# FubarinoMini_v16.net
KiCad netlist of a schematic drawn in EAGLE
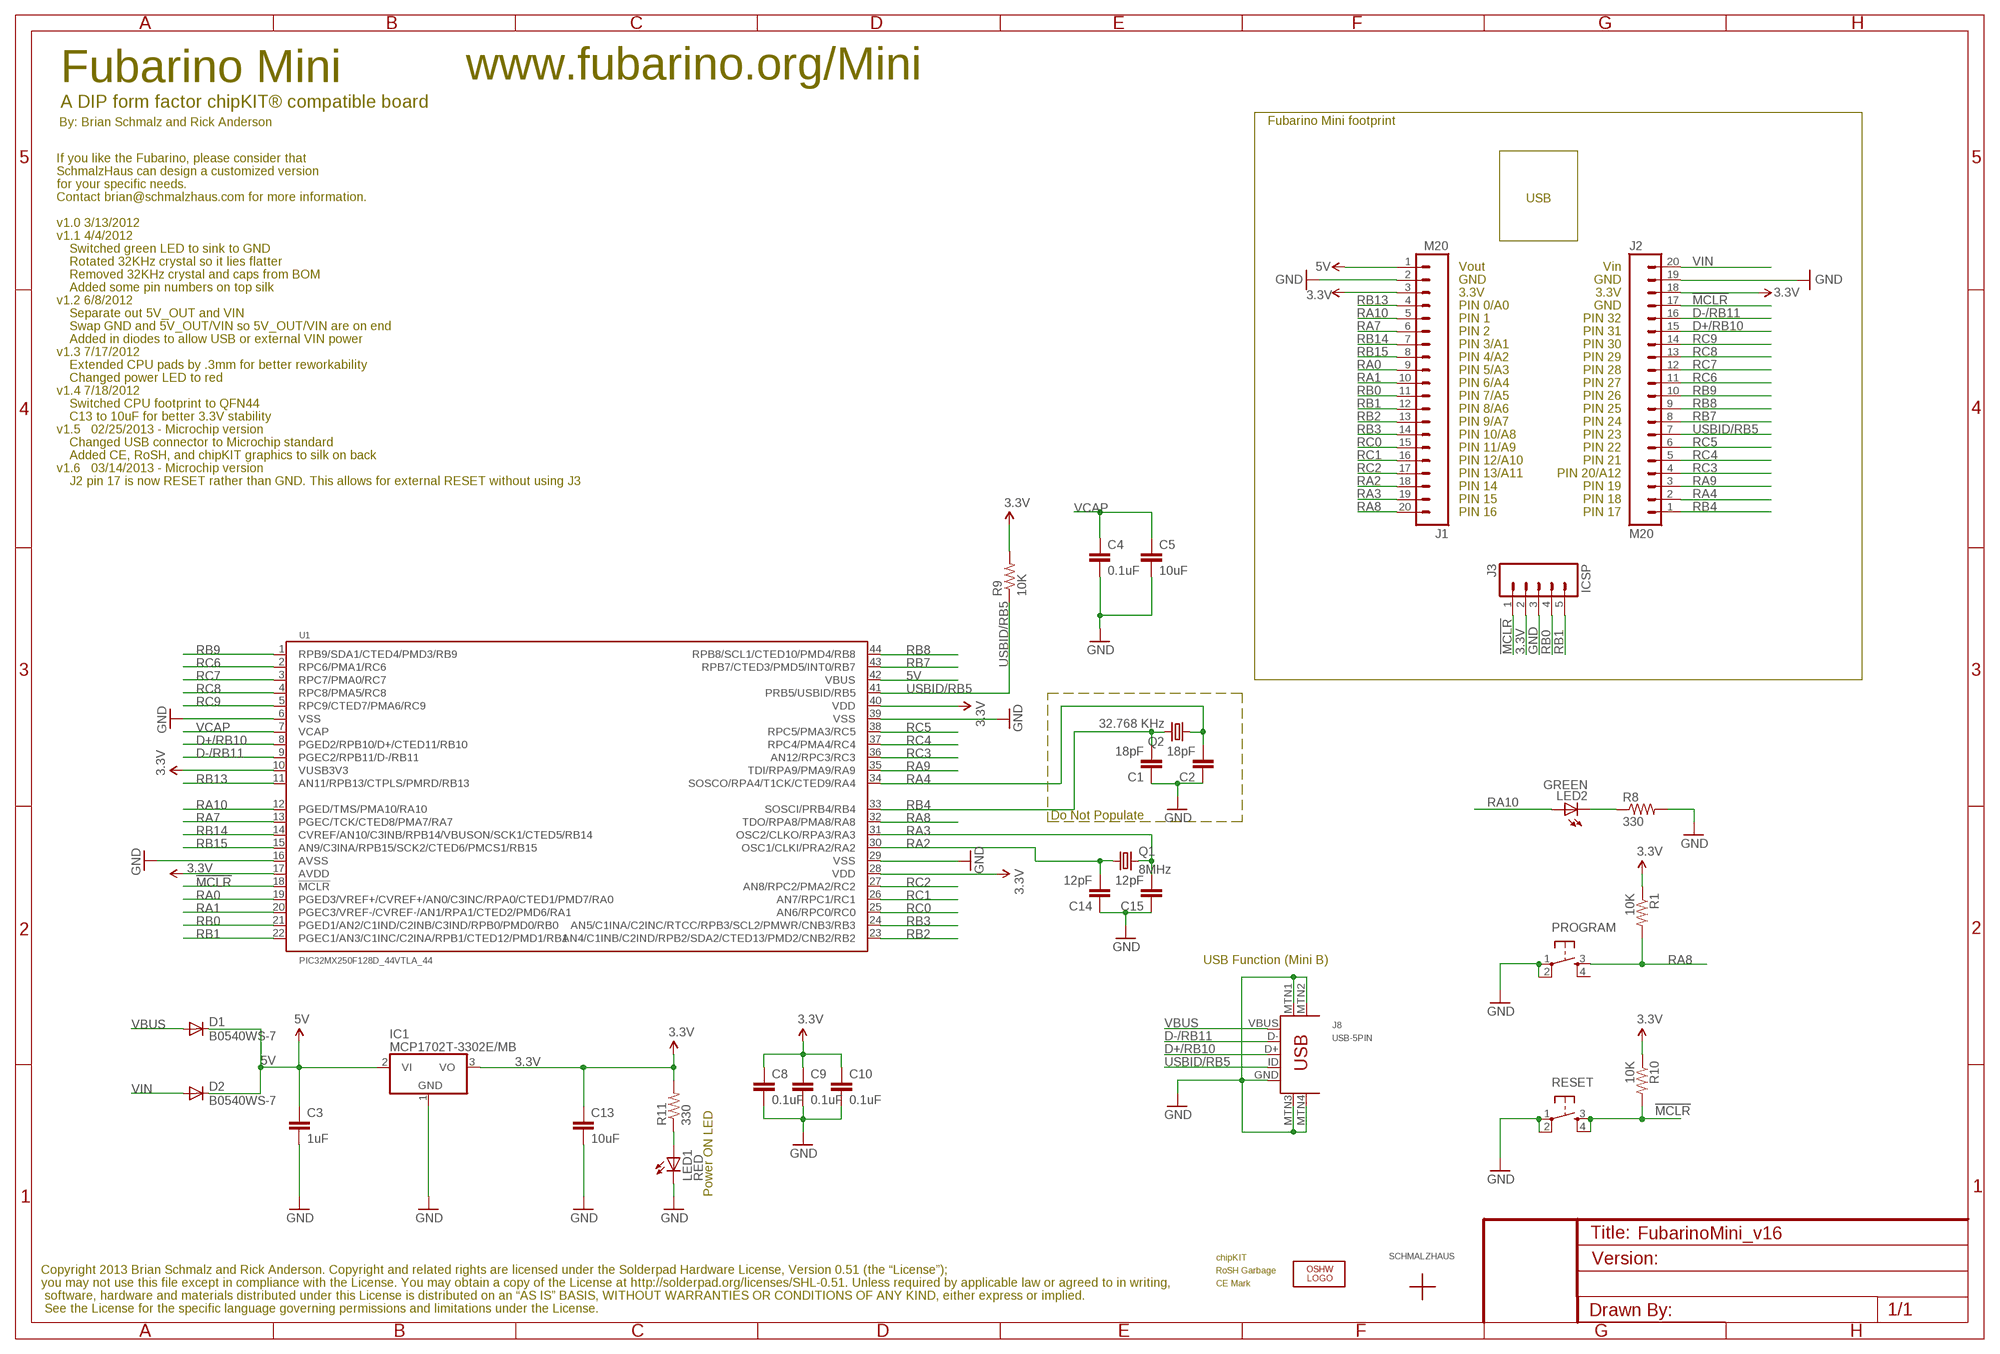
[diagram p0: schematic, sheet 1]

(export (version "E")
  (design (tool "Eeschema 10.0.6"))
  (components
    (comp (ref "C1")
      (value "18pF")
      (footprint "eagle-import:0603-CAP")
      (libsource (lib "eagle-import") (part "SparkFun_CAP0603-CAP"))
    )
    (comp (ref "C2")
      (value "18pF")
      (footprint "eagle-import:0603-CAP")
      (libsource (lib "eagle-import") (part "SparkFun_CAP0603-CAP"))
    )
    (comp (ref "C3")
      (value "1uF")
      (footprint "eagle-import:0603-CAP")
      (libsource (lib "eagle-import") (part "SparkFun_CAP0603-CAP"))
    )
    (comp (ref "C4")
      (value "0.1uF")
      (footprint "eagle-import:0603-CAP")
      (libsource (lib "eagle-import") (part "SparkFun_CAP0603-CAP"))
    )
    (comp (ref "C5")
      (value "10uF")
      (footprint "eagle-import:0805")
      (libsource (lib "eagle-import") (part "CAP0805"))
    )
    (comp (ref "C8")
      (value "0.1uF")
      (footprint "eagle-import:0603-CAP")
      (libsource (lib "eagle-import") (part "SparkFun_CAP0603-CAP"))
    )
    (comp (ref "C9")
      (value "0.1uF")
      (footprint "eagle-import:0603-CAP")
      (libsource (lib "eagle-import") (part "SparkFun_CAP0603-CAP"))
    )
    (comp (ref "C10")
      (value "0.1uF")
      (footprint "eagle-import:0603")
      (libsource (lib "eagle-import") (part "CAP0603"))
    )
    (comp (ref "C13")
      (value "10uF")
      (footprint "eagle-import:0805")
      (libsource (lib "eagle-import") (part "SparkFun02-20-08_CAP0805"))
    )
    (comp (ref "C14")
      (value "12pF")
      (footprint "eagle-import:0603-CAP")
      (libsource (lib "eagle-import") (part "SparkFun_CAP0603-CAP"))
    )
    (comp (ref "C15")
      (value "12pF")
      (footprint "eagle-import:0603-CAP")
      (libsource (lib "eagle-import") (part "SparkFun_CAP0603-CAP"))
    )
    (comp (ref "D1")
      (value "B0540WS-7")
      (footprint "eagle-import:SOD-323")
      (libsource (lib "eagle-import") (part "DIODESOD"))
    )
    (comp (ref "D2")
      (value "B0540WS-7")
      (footprint "eagle-import:SOD-323")
      (libsource (lib "eagle-import") (part "DIODESOD"))
    )
    (comp (ref "IC1")
      (value "MCP1702T-3302E/MB")
      (footprint "eagle-import:SOT89")
      (libsource (lib "eagle-import") (part "MCP1703MB33"))
    )
    (comp (ref "ICSP")
      (value "J3")
      (footprint "eagle-import:1X05_NOSILK")
      (libsource (lib "eagle-import") (part "M05NOSLILK"))
    )
    (comp (ref "J1")
      (value "M20")
      (footprint "eagle-import:1X20_NO_PIN1")
      (libsource (lib "eagle-import") (part "M20"))
    )
    (comp (ref "J2")
      (value "M20")
      (footprint "eagle-import:1X20_NO_PIN1")
      (libsource (lib "eagle-import") (part "M20"))
    )
    (comp (ref "J8")
      (value "USB-5PIN")
      (footprint "eagle-import:USB-MINIB-5PIN-HIROSE-UX60-MB-5ST")
      (libsource (lib "eagle-import") (part "USB-5PIN"))
    )
    (comp (ref "LED1")
      (value "RED")
      (footprint "eagle-import:LED-0603")
      (libsource (lib "eagle-import") (part "LED0603"))
    )
    (comp (ref "LED2")
      (value "GREEN")
      (footprint "eagle-import:LED-0603")
      (libsource (lib "eagle-import") (part "LED0603"))
    )
    (comp (ref "LOGO1")
      (value "OSHW_LOGO_8MILX0070-NT")
      (footprint "eagle-import:OSHW_8X70_NOTEXT")
      (libsource (lib "eagle-import") (part "OSHW_LOGO_8MILX0070-NT"))
    )
    (comp (ref "PROGRAM")
      (value "TAC_SWITCHSND")
      (footprint "eagle-import:TACTILE_SWITCH_SMD")
      (libsource (lib "eagle-import") (part "TAC_SWITCHSND"))
    )
    (comp (ref "Q1")
      (value "8MHz")
      (footprint "eagle-import:NX5032_5MM_3.2MM_CRYSTAL")
      (libsource (lib "eagle-import") (part "CRYSTALNX5032"))
    )
    (comp (ref "Q2")
      (value "32.768 KHz")
      (footprint "eagle-import:TC26H")
      (libsource (lib "eagle-import") (part "CRYSTALTC26H"))
    )
    (comp (ref "R1")
      (value "10K")
      (footprint "eagle-import:0603-RES")
      (libsource (lib "eagle-import") (part "RESISTOR0603-RES"))
    )
    (comp (ref "R8")
      (value "330")
      (footprint "eagle-import:0603-RES")
      (libsource (lib "eagle-import") (part "RESISTOR0603-RES"))
    )
    (comp (ref "R9")
      (value "10K")
      (footprint "eagle-import:0603-RES")
      (libsource (lib "eagle-import") (part "RESISTOR0603-RES"))
    )
    (comp (ref "R10")
      (value "10K")
      (footprint "eagle-import:0603-RES")
      (libsource (lib "eagle-import") (part "RESISTOR0603-RES"))
    )
    (comp (ref "R11")
      (value "330")
      (footprint "eagle-import:0603-RES")
      (libsource (lib "eagle-import") (part "RESISTOR0603-RES"))
    )
    (comp (ref "RESET")
      (value "TAC_SWITCHSND")
      (footprint "eagle-import:TACTILE_SWITCH_SMD")
      (libsource (lib "eagle-import") (part "TAC_SWITCHSND"))
    )
    (comp (ref "U$1")
      (value "SCHMALZHAUSSCHMALZHAUS_SMALL")
      (footprint "eagle-import:SCHMALZHAUS_SMALL")
      (libsource (lib "eagle-import") (part "SCHMALZHAUSSCHMALZHAUS_SMALL"))
    )
    (comp (ref "U$2")
      (value "CE_MARK5MM")
      (footprint "eagle-import:CE_5MM")
      (libsource (lib "eagle-import") (part "CE_MARK5MM"))
    )
    (comp (ref "U$3")
      (value "ROSH_GARBAGE")
      (footprint "eagle-import:ROHS_GARBAGE_5MM")
      (libsource (lib "eagle-import") (part "ROSH_GARBAGE"))
    )
    (comp (ref "U$4")
      (value "CHIPKIT2MM")
      (footprint "eagle-import:CHIPKIT_2MM")
      (libsource (lib "eagle-import") (part "CHIPKIT2MM"))
    )
    (comp (ref "U1")
      (value "PIC32MX250F128D_44VTLA_44")
      (footprint "eagle-import:QFN-44-8X8-NOPAD")
      (libsource (lib "eagle-import") (part "PIC32MX2XX_44QFN44"))
    )
  )
  (nets
    (net (code "1") (name "/D+{slash}RB10") (class "Default")
      (node (ref "J2") (pin "15") (pinfunction "15_15") (pintype "passive"))
      (node (ref "J8") (pin "D+") (pinfunction "D+_D+") (pintype "bidirectional"))
      (node (ref "U1") (pin "8") (pinfunction "PGED2/RPB10/D+/CTED11/RB10_8") (pintype "bidirectional"))
    )
    (net (code "2") (name "/D-{slash}RB11") (class "Default")
      (node (ref "J2") (pin "16") (pinfunction "16_16") (pintype "passive"))
      (node (ref "J8") (pin "D-") (pinfunction "D-_D-") (pintype "bidirectional"))
      (node (ref "U1") (pin "9") (pinfunction "PGEC2/RPB11/D-/RB11_9") (pintype "bidirectional"))
    )
    (net (code "3") (name "/RA0") (class "Default")
      (node (ref "J1") (pin "9") (pinfunction "9_9") (pintype "passive"))
      (node (ref "U1") (pin "19") (pinfunction "PGED3/VREF+/CVREF+/AN0/C3INC/RPA0/CTED1/PMD7/RA0_19") (pintype "bidirectional"))
    )
    (net (code "4") (name "/RA1") (class "Default")
      (node (ref "J1") (pin "10") (pinfunction "10_10") (pintype "passive"))
      (node (ref "U1") (pin "20") (pinfunction "PGEC3/VREF-/CVREF-/AN1/RPA1/CTED2/PMD6/RA1_20") (pintype "bidirectional"))
    )
    (net (code "5") (name "/RA2") (class "Default")
      (node (ref "C14") (pin "2") (pinfunction "2_2") (pintype "passive"))
      (node (ref "J1") (pin "18") (pinfunction "18_18") (pintype "passive"))
      (node (ref "Q1") (pin "1") (pinfunction "1_1") (pintype "passive"))
      (node (ref "U1") (pin "30") (pinfunction "OSC1/CLKI/PRA2/RA2_30") (pintype "bidirectional"))
    )
    (net (code "6") (name "/RA3") (class "Default")
      (node (ref "C15") (pin "2") (pinfunction "2_2") (pintype "passive"))
      (node (ref "J1") (pin "19") (pinfunction "19_19") (pintype "passive"))
      (node (ref "Q1") (pin "2") (pinfunction "2_2") (pintype "passive"))
      (node (ref "U1") (pin "31") (pinfunction "OSC2/CLKO/RPA3/RA3_31") (pintype "bidirectional"))
    )
    (net (code "7") (name "/RA4") (class "Default")
      (node (ref "C2") (pin "2") (pinfunction "2_2") (pintype "passive"))
      (node (ref "J2") (pin "2") (pinfunction "2_2") (pintype "passive"))
      (node (ref "Q2") (pin "1") (pinfunction "1_1") (pintype "passive"))
      (node (ref "U1") (pin "34") (pinfunction "SOSCO/RPA4/T1CK/CTED9/RA4_34") (pintype "bidirectional"))
    )
    (net (code "8") (name "/RA7") (class "Default")
      (node (ref "J1") (pin "6") (pinfunction "6_6") (pintype "passive"))
      (node (ref "U1") (pin "13") (pinfunction "PGEC/TCK/CTED8/PMA7/RA7_13") (pintype "bidirectional"))
    )
    (net (code "9") (name "/RA8") (class "Default")
      (node (ref "J1") (pin "20") (pinfunction "20_20") (pintype "passive"))
      (node (ref "PROGRAM") (pin "3") (pinfunction "3_3") (pintype "passive"))
      (node (ref "R1") (pin "2") (pinfunction "2_2") (pintype "passive"))
      (node (ref "U1") (pin "32") (pinfunction "TDO/RPA8/PMA8/RA8_32") (pintype "bidirectional"))
    )
    (net (code "10") (name "/RA9") (class "Default")
      (node (ref "J2") (pin "3") (pinfunction "3_3") (pintype "passive"))
      (node (ref "U1") (pin "35") (pinfunction "TDI/RPA9/PMA9/RA9_35") (pintype "bidirectional"))
    )
    (net (code "11") (name "/RA10") (class "Default")
      (node (ref "J1") (pin "5") (pinfunction "5_5") (pintype "passive"))
      (node (ref "LED2") (pin "A") (pinfunction "A_A") (pintype "passive"))
      (node (ref "U1") (pin "12") (pinfunction "PGED/TMS/PMA10/RA10_12") (pintype "bidirectional"))
    )
    (net (code "12") (name "/RB0") (class "Default")
      (node (ref "ICSP") (pin "4") (pinfunction "4_4") (pintype "passive"))
      (node (ref "J1") (pin "11") (pinfunction "11_11") (pintype "passive"))
      (node (ref "U1") (pin "21") (pinfunction "PGED1/AN2/C1IND/C2INB/C3IND/RPB0/PMD0/RB0_21") (pintype "bidirectional"))
    )
    (net (code "13") (name "/RB1") (class "Default")
      (node (ref "ICSP") (pin "5") (pinfunction "5_5") (pintype "passive"))
      (node (ref "J1") (pin "12") (pinfunction "12_12") (pintype "passive"))
      (node (ref "U1") (pin "22") (pinfunction "PGEC1/AN3/C1INC/C2INA/RPB1/CTED12/PMD1/RB1_22") (pintype "bidirectional"))
    )
    (net (code "14") (name "/RB2") (class "Default")
      (node (ref "J1") (pin "13") (pinfunction "13_13") (pintype "passive"))
      (node (ref "U1") (pin "23") (pinfunction "AN4/C1INB/C2IND/RPB2/SDA2/CTED13/PMD2/CNB2/RB2_23") (pintype "bidirectional"))
    )
    (net (code "15") (name "/RB3") (class "Default")
      (node (ref "J1") (pin "14") (pinfunction "14_14") (pintype "passive"))
      (node (ref "U1") (pin "24") (pinfunction "AN5/C1INA/C2INC/RTCC/RPB3/SCL2/PMWR/CNB3/RB3_24") (pintype "bidirectional"))
    )
    (net (code "16") (name "/RB4") (class "Default")
      (node (ref "C1") (pin "2") (pinfunction "2_2") (pintype "passive"))
      (node (ref "J2") (pin "1") (pinfunction "1_1") (pintype "passive"))
      (node (ref "Q2") (pin "2") (pinfunction "2_2") (pintype "passive"))
      (node (ref "U1") (pin "33") (pinfunction "SOSCI/PRB4/RB4_33") (pintype "bidirectional"))
    )
    (net (code "17") (name "/RB7") (class "Default")
      (node (ref "J2") (pin "8") (pinfunction "8_8") (pintype "passive"))
      (node (ref "U1") (pin "43") (pinfunction "RPB7/CTED3/PMD5/INT0/RB7_43") (pintype "bidirectional"))
    )
    (net (code "18") (name "/RB8") (class "Default")
      (node (ref "J2") (pin "9") (pinfunction "9_9") (pintype "passive"))
      (node (ref "U1") (pin "44") (pinfunction "RPB8/SCL1/CTED10/PMD4/RB8_44") (pintype "bidirectional"))
    )
    (net (code "19") (name "/RB9") (class "Default")
      (node (ref "J2") (pin "10") (pinfunction "10_10") (pintype "passive"))
      (node (ref "U1") (pin "1") (pinfunction "RPB9/SDA1/CTED4/PMD3/RB9_1") (pintype "bidirectional"))
    )
    (net (code "20") (name "/RB13") (class "Default")
      (node (ref "J1") (pin "4") (pinfunction "4_4") (pintype "passive"))
      (node (ref "U1") (pin "11") (pinfunction "AN11/RPB13/CTPLS/PMRD/RB13_11") (pintype "bidirectional"))
    )
    (net (code "21") (name "/RB14") (class "Default")
      (node (ref "J1") (pin "7") (pinfunction "7_7") (pintype "passive"))
      (node (ref "U1") (pin "14") (pinfunction "CVREF/AN10/C3INB/RPB14/VBUSON/SCK1/CTED5/RB14_14") (pintype "bidirectional"))
    )
    (net (code "22") (name "/RB15") (class "Default")
      (node (ref "J1") (pin "8") (pinfunction "8_8") (pintype "passive"))
      (node (ref "U1") (pin "15") (pinfunction "AN9/C3INA/RPB15/SCK2/CTED6/PMCS1/RB15_15") (pintype "bidirectional"))
    )
    (net (code "23") (name "/RC0") (class "Default")
      (node (ref "J1") (pin "15") (pinfunction "15_15") (pintype "passive"))
      (node (ref "U1") (pin "25") (pinfunction "AN6/RPC0/RC0_25") (pintype "bidirectional"))
    )
    (net (code "24") (name "/RC1") (class "Default")
      (node (ref "J1") (pin "16") (pinfunction "16_16") (pintype "passive"))
      (node (ref "U1") (pin "26") (pinfunction "AN7/RPC1/RC1_26") (pintype "bidirectional"))
    )
    (net (code "25") (name "/RC2") (class "Default")
      (node (ref "J1") (pin "17") (pinfunction "17_17") (pintype "passive"))
      (node (ref "U1") (pin "27") (pinfunction "AN8/RPC2/PMA2/RC2_27") (pintype "bidirectional"))
    )
    (net (code "26") (name "/RC3") (class "Default")
      (node (ref "J2") (pin "4") (pinfunction "4_4") (pintype "passive"))
      (node (ref "U1") (pin "36") (pinfunction "AN12/RPC3/RC3_36") (pintype "bidirectional"))
    )
    (net (code "27") (name "/RC4") (class "Default")
      (node (ref "J2") (pin "5") (pinfunction "5_5") (pintype "passive"))
      (node (ref "U1") (pin "37") (pinfunction "RPC4/PMA4/RC4_37") (pintype "bidirectional"))
    )
    (net (code "28") (name "/RC5") (class "Default")
      (node (ref "J2") (pin "6") (pinfunction "6_6") (pintype "passive"))
      (node (ref "U1") (pin "38") (pinfunction "RPC5/PMA3/RC5_38") (pintype "bidirectional"))
    )
    (net (code "29") (name "/RC6") (class "Default")
      (node (ref "J2") (pin "11") (pinfunction "11_11") (pintype "passive"))
      (node (ref "U1") (pin "2") (pinfunction "RPC6/PMA1/RC6_2") (pintype "bidirectional"))
    )
    (net (code "30") (name "/RC7") (class "Default")
      (node (ref "J2") (pin "12") (pinfunction "12_12") (pintype "passive"))
      (node (ref "U1") (pin "3") (pinfunction "RPC7/PMA0/RC7_3") (pintype "bidirectional"))
    )
    (net (code "31") (name "/RC8") (class "Default")
      (node (ref "J2") (pin "13") (pinfunction "13_13") (pintype "passive"))
      (node (ref "U1") (pin "4") (pinfunction "RPC8/PMA5/RC8_4") (pintype "bidirectional"))
    )
    (net (code "32") (name "/RC9") (class "Default")
      (node (ref "J2") (pin "14") (pinfunction "14_14") (pintype "passive"))
      (node (ref "U1") (pin "5") (pinfunction "RPC9/CTED7/PMA6/RC9_5") (pintype "bidirectional"))
    )
    (net (code "33") (name "/USBID{slash}RB5") (class "Default")
      (node (ref "J2") (pin "7") (pinfunction "7_7") (pintype "passive"))
      (node (ref "J8") (pin "ID") (pinfunction "ID_ID") (pintype "bidirectional"))
      (node (ref "R9") (pin "1") (pinfunction "1_1") (pintype "passive"))
      (node (ref "U1") (pin "41") (pinfunction "PRB5/USBID/RB5_41") (pintype "bidirectional"))
    )
    (net (code "34") (name "/VBUS") (class "Default")
      (node (ref "D1") (pin "2") (pinfunction "A_2") (pintype "passive"))
      (node (ref "J8") (pin "VBUS") (pinfunction "VBUS_VBUS") (pintype "bidirectional"))
    )
    (net (code "35") (name "/VCAP") (class "Default")
      (node (ref "C4") (pin "1") (pinfunction "1_1") (pintype "passive"))
      (node (ref "C5") (pin "1") (pinfunction "1_1") (pintype "passive"))
      (node (ref "U1") (pin "7") (pinfunction "VCAP_7") (pintype "bidirectional"))
    )
    (net (code "36") (name "/VIN") (class "Default")
      (node (ref "D2") (pin "2") (pinfunction "A_2") (pintype "passive"))
      (node (ref "J2") (pin "20") (pinfunction "20_20") (pintype "passive"))
    )
    (net (code "37") (name "/~{MCLR}") (class "Default")
      (node (ref "ICSP") (pin "1") (pinfunction "1_1") (pintype "passive"))
      (node (ref "J2") (pin "17") (pinfunction "17_17") (pintype "passive"))
      (node (ref "R10") (pin "2") (pinfunction "2_2") (pintype "passive"))
      (node (ref "RESET") (pin "3") (pinfunction "3_3") (pintype "passive"))
      (node (ref "RESET") (pin "4") (pinfunction "4_4") (pintype "passive"))
      (node (ref "U1") (pin "18") (pinfunction "~{MCLR}_18") (pintype "bidirectional"))
    )
    (net (code "38") (name "3.3V") (class "Default")
      (node (ref "C10") (pin "1") (pinfunction "1_1") (pintype "passive"))
      (node (ref "C13") (pin "1") (pinfunction "1_1") (pintype "passive"))
      (node (ref "C8") (pin "1") (pinfunction "1_1") (pintype "passive"))
      (node (ref "C9") (pin "1") (pinfunction "1_1") (pintype "passive"))
      (node (ref "IC1") (pin "3") (pinfunction "VO_3") (pintype "passive"))
      (node (ref "ICSP") (pin "2") (pinfunction "2_2") (pintype "passive"))
      (node (ref "J1") (pin "3") (pinfunction "3_3") (pintype "passive"))
      (node (ref "J2") (pin "18") (pinfunction "18_18") (pintype "passive"))
      (node (ref "R1") (pin "1") (pinfunction "1_1") (pintype "passive"))
      (node (ref "R10") (pin "1") (pinfunction "1_1") (pintype "passive"))
      (node (ref "R11") (pin "2") (pinfunction "2_2") (pintype "passive"))
      (node (ref "R9") (pin "2") (pinfunction "2_2") (pintype "passive"))
      (node (ref "U1") (pin "10") (pinfunction "VUSB3V3_10") (pintype "bidirectional"))
      (node (ref "U1") (pin "17") (pinfunction "AVDD_17") (pintype "bidirectional"))
      (node (ref "U1") (pin "28") (pinfunction "VDD_28") (pintype "bidirectional"))
      (node (ref "U1") (pin "40") (pinfunction "VDD_40") (pintype "bidirectional"))
    )
    (net (code "39") (name "5V") (class "Default")
      (node (ref "C3") (pin "1") (pinfunction "1_1") (pintype "passive"))
      (node (ref "D1") (pin "1") (pinfunction "C_1") (pintype "passive"))
      (node (ref "D2") (pin "1") (pinfunction "C_1") (pintype "passive"))
      (node (ref "IC1") (pin "2") (pinfunction "VI_2") (pintype "input"))
      (node (ref "IC1") (pin "2@1") (pinfunction "VI1_2@1") (pintype "input"))
      (node (ref "J1") (pin "1") (pinfunction "1_1") (pintype "passive"))
      (node (ref "U1") (pin "42") (pinfunction "VBUS_42") (pintype "bidirectional"))
    )
    (net (code "40") (name "GND") (class "Default")
      (node (ref "C1") (pin "1") (pinfunction "1_1") (pintype "passive"))
      (node (ref "C10") (pin "2") (pinfunction "2_2") (pintype "passive"))
      (node (ref "C13") (pin "2") (pinfunction "2_2") (pintype "passive"))
      (node (ref "C14") (pin "1") (pinfunction "1_1") (pintype "passive"))
      (node (ref "C15") (pin "1") (pinfunction "1_1") (pintype "passive"))
      (node (ref "C2") (pin "1") (pinfunction "1_1") (pintype "passive"))
      (node (ref "C3") (pin "2") (pinfunction "2_2") (pintype "passive"))
      (node (ref "C4") (pin "2") (pinfunction "2_2") (pintype "passive"))
      (node (ref "C5") (pin "2") (pinfunction "2_2") (pintype "passive"))
      (node (ref "C8") (pin "2") (pinfunction "2_2") (pintype "passive"))
      (node (ref "C9") (pin "2") (pinfunction "2_2") (pintype "passive"))
      (node (ref "IC1") (pin "1") (pinfunction "GND_1") (pintype "passive"))
      (node (ref "ICSP") (pin "3") (pinfunction "3_3") (pintype "passive"))
      (node (ref "J1") (pin "2") (pinfunction "2_2") (pintype "passive"))
      (node (ref "J2") (pin "19") (pinfunction "19_19") (pintype "passive"))
      (node (ref "J8") (pin "GND") (pinfunction "GND_GND") (pintype "bidirectional"))
      (node (ref "J8") (pin "MTN1") (pinfunction "MTN1_MTN1") (pintype "bidirectional"))
      (node (ref "J8") (pin "MTN2") (pinfunction "MTN2_MTN2") (pintype "bidirectional"))
      (node (ref "J8") (pin "MTN3") (pinfunction "MTN3_MTN3") (pintype "bidirectional"))
      (node (ref "J8") (pin "MTN4") (pinfunction "MTN4_MTN4") (pintype "bidirectional"))
      (node (ref "LED1") (pin "C") (pinfunction "C_C") (pintype "passive"))
      (node (ref "PROGRAM") (pin "1") (pinfunction "1_1") (pintype "passive"))
      (node (ref "PROGRAM") (pin "2") (pinfunction "2_2") (pintype "passive"))
      (node (ref "R8") (pin "2") (pinfunction "2_2") (pintype "passive"))
      (node (ref "RESET") (pin "1") (pinfunction "1_1") (pintype "passive"))
      (node (ref "RESET") (pin "2") (pinfunction "2_2") (pintype "passive"))
      (node (ref "U1") (pin "16") (pinfunction "AVSS_16") (pintype "bidirectional"))
      (node (ref "U1") (pin "29") (pinfunction "VSS_29") (pintype "bidirectional"))
      (node (ref "U1") (pin "39") (pinfunction "VSS_39") (pintype "bidirectional"))
      (node (ref "U1") (pin "6") (pinfunction "VSS_6") (pintype "bidirectional"))
    )
    (net (code "41") (name "Net-(LED1-PadA)") (class "Default")
      (node (ref "LED1") (pin "A") (pinfunction "A_A") (pintype "passive"))
      (node (ref "R11") (pin "1") (pinfunction "1_1") (pintype "passive"))
    )
    (net (code "42") (name "Net-(LED2-PadC)") (class "Default")
      (node (ref "LED2") (pin "C") (pinfunction "C_C") (pintype "passive"))
      (node (ref "R8") (pin "1") (pinfunction "1_1") (pintype "passive"))
    )
    (net (code "43") (name "unconnected-(PROGRAM-Pad4)") (class "Default")
      (node (ref "PROGRAM") (pin "4") (pinfunction "4_4") (pintype "passive"))
    )
  )
)
